# Schematic.net
KiCad netlist of a schematic drawn in EAGLE
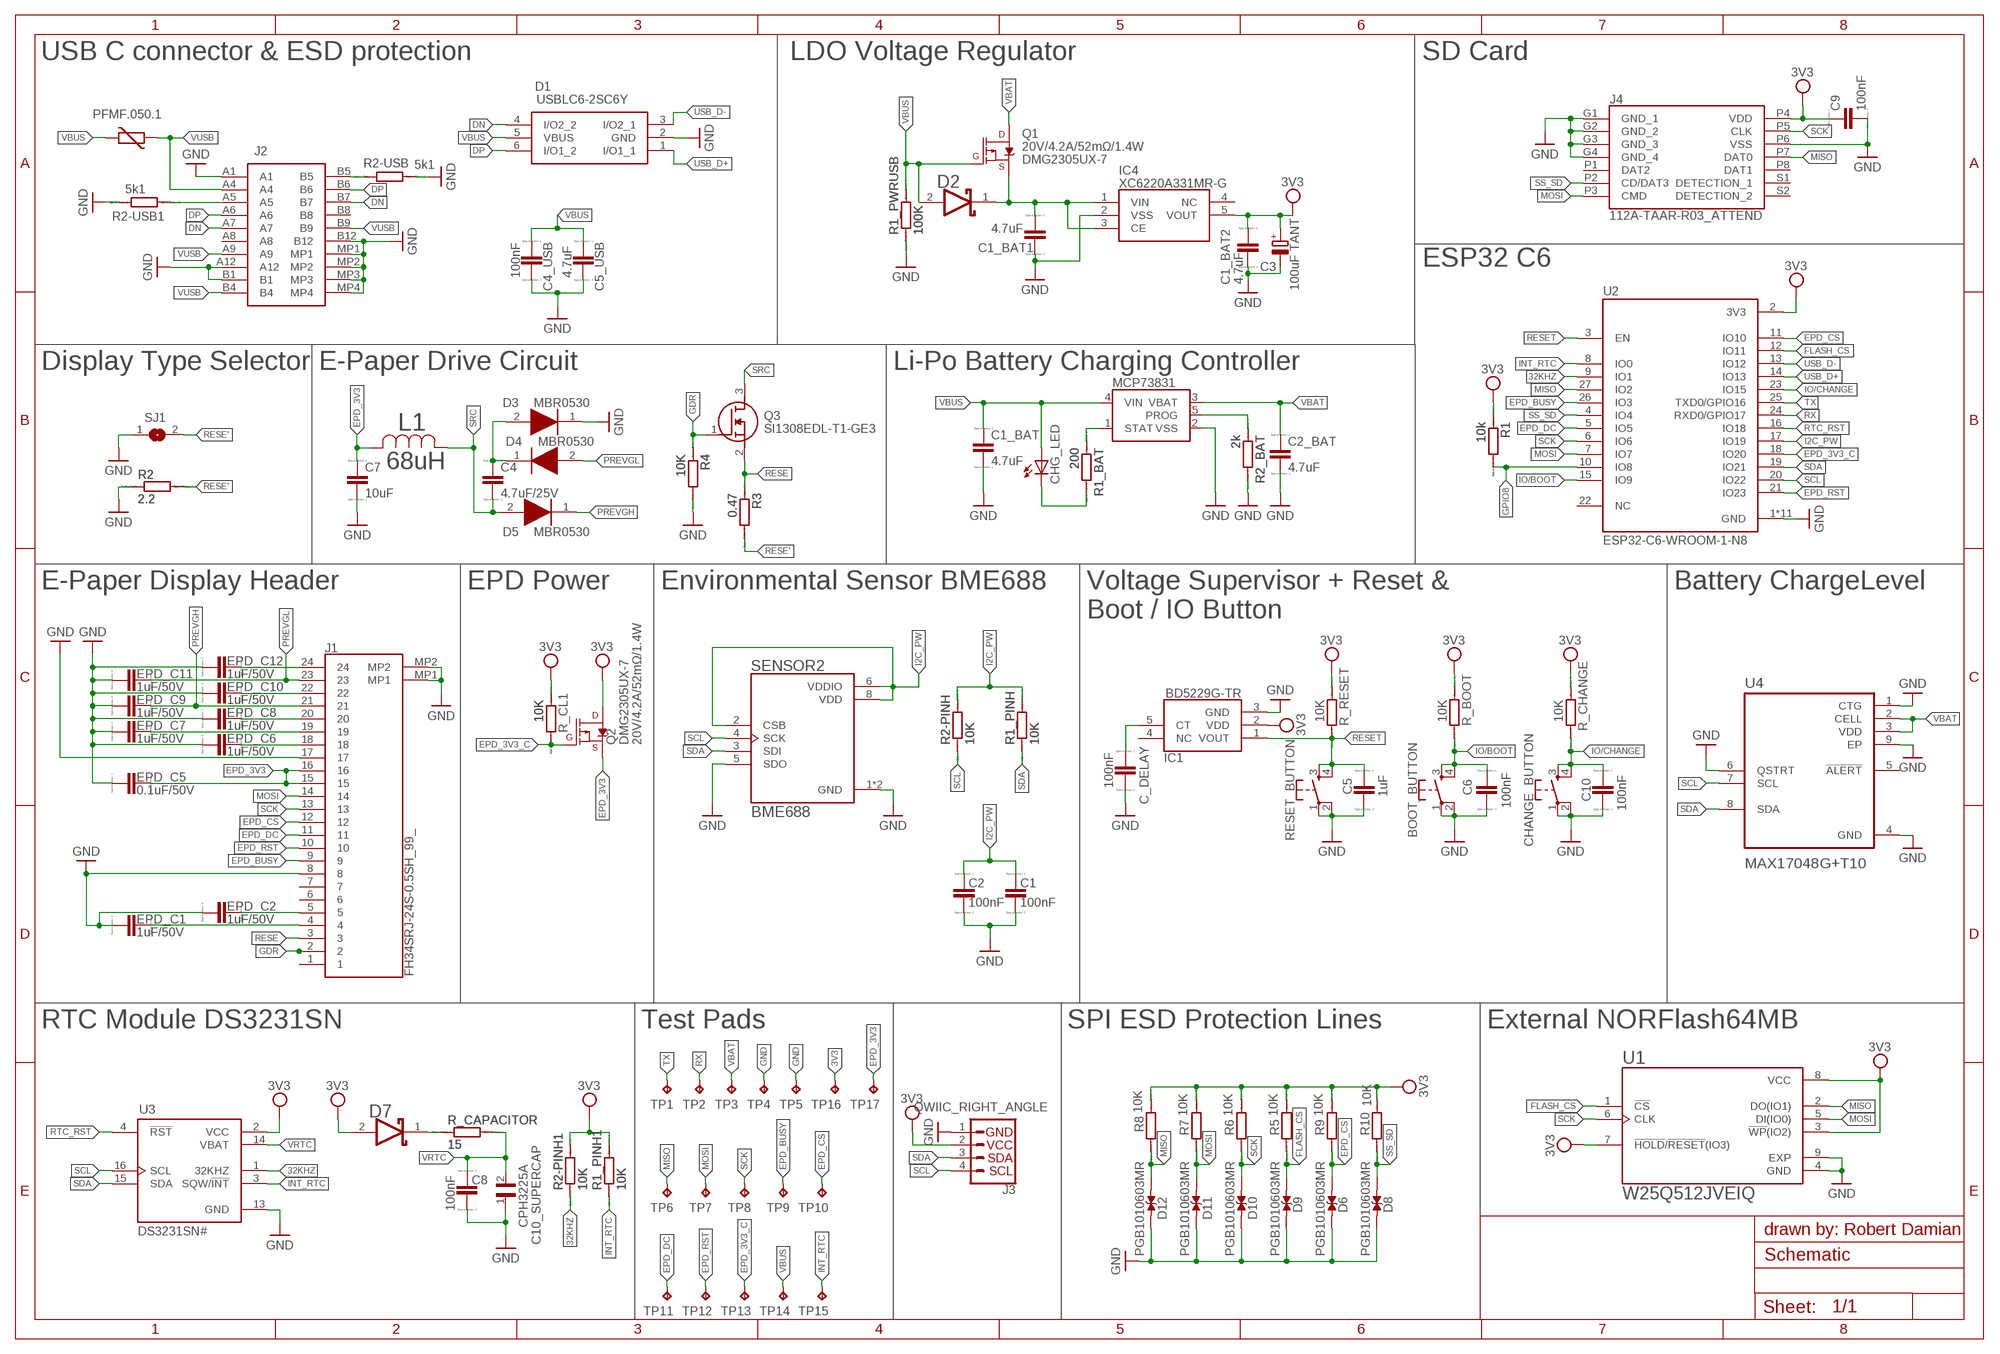
[diagram p0: schematic, sheet 1]

(export (version "E")
  (design (tool "Eeschema 10.0.6"))
  (components
    (comp (ref "BOOT_BUTTON")
      (value "BUTTON_CUSYOMV1")
      (footprint "eagle-import:MYBUTTON")
      (libsource (lib "eagle-import") (part "BUTTON_CUSYOMV1"))
    )
    (comp (ref "C1")
      (value "100nF")
      (footprint "eagle-import:EAGLE-LTSPICE_C0402")
      (libsource (lib "eagle-import") (part "EAGLE-LTSPICE_CC0402"))
    )
    (comp (ref "C1_BAT")
      (value "4.7uF")
      (footprint "eagle-import:EAGLE-LTSPICE_C0402")
      (libsource (lib "eagle-import") (part "EAGLE-LTSPICE_CC0402"))
    )
    (comp (ref "C1_BAT1")
      (value "4.7uF")
      (footprint "eagle-import:EAGLE-LTSPICE_C0402")
      (libsource (lib "eagle-import") (part "EAGLE-LTSPICE_CC0402"))
    )
    (comp (ref "C1_BAT2")
      (value "4.7uF")
      (footprint "eagle-import:EAGLE-LTSPICE_C0402")
      (libsource (lib "eagle-import") (part "EAGLE-LTSPICE_CC0402"))
    )
    (comp (ref "C2")
      (value "100nF")
      (footprint "eagle-import:EAGLE-LTSPICE_C0402")
      (libsource (lib "eagle-import") (part "EAGLE-LTSPICE_CC0402"))
    )
    (comp (ref "C2_BAT")
      (value "4.7uF")
      (footprint "eagle-import:EAGLE-LTSPICE_C0402")
      (libsource (lib "eagle-import") (part "EAGLE-LTSPICE_CC0402"))
    )
    (comp (ref "C3")
      (value "100uF TANT")
      (footprint "eagle-import:RCL_CT3528")
      (libsource (lib "eagle-import") (part "RCL_CPOL-EUCT3528"))
    )
    (comp (ref "C4")
      (value "4.7uF/25V")
      (footprint "eagle-import:EAGLE-LTSPICE_C0402")
      (libsource (lib "eagle-import") (part "EAGLE-LTSPICE_CC0402"))
    )
    (comp (ref "C4_USB")
      (value "100nF")
      (footprint "eagle-import:EAGLE-LTSPICE_C0402")
      (libsource (lib "eagle-import") (part "EAGLE-LTSPICE_CC0402"))
    )
    (comp (ref "C5")
      (value "1uF")
      (footprint "eagle-import:EAGLE-LTSPICE_C0402")
      (libsource (lib "eagle-import") (part "EAGLE-LTSPICE_CC0402"))
    )
    (comp (ref "C5_USB")
      (value "4.7uF")
      (footprint "eagle-import:EAGLE-LTSPICE_C0402")
      (libsource (lib "eagle-import") (part "EAGLE-LTSPICE_CC0402"))
    )
    (comp (ref "C6")
      (value "100nF")
      (footprint "eagle-import:EAGLE-LTSPICE_C0402")
      (libsource (lib "eagle-import") (part "EAGLE-LTSPICE_CC0402"))
    )
    (comp (ref "C7")
      (value "10uF")
      (footprint "eagle-import:EAGLE-LTSPICE_C0402")
      (libsource (lib "eagle-import") (part "EAGLE-LTSPICE_CC0402"))
    )
    (comp (ref "C8")
      (value "100nF")
      (footprint "eagle-import:EAGLE-LTSPICE_C0402")
      (libsource (lib "eagle-import") (part "EAGLE-LTSPICE_CC0402"))
    )
    (comp (ref "C9")
      (value "100nF")
      (footprint "eagle-import:EAGLE-LTSPICE_C0402")
      (libsource (lib "eagle-import") (part "EAGLE-LTSPICE_CC0402"))
    )
    (comp (ref "C10")
      (value "100nF")
      (footprint "eagle-import:EAGLE-LTSPICE_C0402")
      (libsource (lib "eagle-import") (part "EAGLE-LTSPICE_CC0402"))
    )
    (comp (ref "C10_SUPERCAP")
      (value "CPH3225A")
      (footprint "eagle-import:CAPCP3225X100N")
      (fields (field (name "MF") "Seiko Instruments"))
      (libsource (lib "eagle-import") (part "CPH3225A"))
    )
    (comp (ref "CHANGE_BUTTON")
      (value "BUTTON_CUSYOMV1")
      (footprint "eagle-import:MYBUTTON")
      (libsource (lib "eagle-import") (part "BUTTON_CUSYOMV1"))
    )
    (comp (ref "CHG_LED")
      (value "ADAFRUIT_LEDCHIP-LED0603")
      (footprint "eagle-import:ADAFRUIT_CHIP-LED0603")
      (libsource (lib "eagle-import") (part "ADAFRUIT_LEDCHIP-LED0603"))
    )
    (comp (ref "C_DELAY")
      (value "100nF")
      (footprint "eagle-import:EAGLE-LTSPICE_C0402")
      (libsource (lib "eagle-import") (part "EAGLE-LTSPICE_CC0402"))
    )
    (comp (ref "D1")
      (value "USBLC6-2SC6Y")
      (footprint "eagle-import:SOT95P280X145-6N")
      (fields (field (name "MF") "STMicroelectronics"))
      (libsource (lib "eagle-import") (part "USBLC6-2SC6Y"))
    )
    (comp (ref "D2")
      (value "SD0805S020S1R0")
      (footprint "eagle-import:ESP32_WROVER_AVX---SD0805S020S1R0_AVX_SD0805S020S1R0_0")
      (fields
        (field (name "DIGIKEY_PART_NUMBER") "478-7800-1-ND")
        (field (name "MF") "AVX")
        (field (name "MOUSER_PART_NUMBER") "581-SD0805S020S1R0")
      )
      (libsource (lib "eagle-import") (part "ESP32_WROVER_AVX---SD0805S020S1R0_AVX_SD0805S020S1R0_0_0AVX_SD0805S020S1R0_0_0"))
    )
    (comp (ref "D3")
      (value "MBR0530")
      (footprint "eagle-import:SOD3716X135N")
      (fields (field (name "MF") "ON Semiconductor"))
      (libsource (lib "eagle-import") (part "MBR0530"))
    )
    (comp (ref "D4")
      (value "MBR0530")
      (footprint "eagle-import:SOD3716X135N")
      (fields (field (name "MF") "ON Semiconductor"))
      (libsource (lib "eagle-import") (part "MBR0530"))
    )
    (comp (ref "D5")
      (value "MBR0530")
      (footprint "eagle-import:SOD3716X135N")
      (fields (field (name "MF") "ON Semiconductor"))
      (libsource (lib "eagle-import") (part "MBR0530"))
    )
    (comp (ref "D6")
      (value "PGB1010603MR")
      (footprint "eagle-import:DIOC1608X36N")
      (fields (field (name "MF") "Littelfuse Inc."))
      (libsource (lib "eagle-import") (part "PGB1010603MR"))
    )
    (comp (ref "D7")
      (value "SD0805S020S1R0")
      (footprint "eagle-import:ESP32_WROVER_AVX---SD0805S020S1R0_AVX_SD0805S020S1R0_0")
      (fields
        (field (name "DIGIKEY_PART_NUMBER") "478-7800-1-ND")
        (field (name "MF") "AVX")
        (field (name "MOUSER_PART_NUMBER") "581-SD0805S020S1R0")
      )
      (libsource (lib "eagle-import") (part "ESP32_WROVER_AVX---SD0805S020S1R0_AVX_SD0805S020S1R0_0_0AVX_SD0805S020S1R0_0_0"))
    )
    (comp (ref "D8")
      (value "PGB1010603MR")
      (footprint "eagle-import:DIOC1608X36N")
      (fields (field (name "MF") "Littelfuse Inc."))
      (libsource (lib "eagle-import") (part "PGB1010603MR"))
    )
    (comp (ref "D9")
      (value "PGB1010603MR")
      (footprint "eagle-import:DIOC1608X36N")
      (fields (field (name "MF") "Littelfuse Inc."))
      (libsource (lib "eagle-import") (part "PGB1010603MR"))
    )
    (comp (ref "D10")
      (value "PGB1010603MR")
      (footprint "eagle-import:DIOC1608X36N")
      (fields (field (name "MF") "Littelfuse Inc."))
      (libsource (lib "eagle-import") (part "PGB1010603MR"))
    )
    (comp (ref "D11")
      (value "PGB1010603MR")
      (footprint "eagle-import:DIOC1608X36N")
      (fields (field (name "MF") "Littelfuse Inc."))
      (libsource (lib "eagle-import") (part "PGB1010603MR"))
    )
    (comp (ref "D12")
      (value "PGB1010603MR")
      (footprint "eagle-import:DIOC1608X36N")
      (fields (field (name "MF") "Littelfuse Inc."))
      (libsource (lib "eagle-import") (part "PGB1010603MR"))
    )
    (comp (ref "EPD_C1")
      (value "1uF/50V")
      (footprint "eagle-import:EAGLE-LTSPICE_C0402")
      (libsource (lib "eagle-import") (part "EAGLE-LTSPICE_CC0402"))
    )
    (comp (ref "EPD_C2")
      (value "1uF/50V")
      (footprint "eagle-import:EAGLE-LTSPICE_C0402")
      (libsource (lib "eagle-import") (part "EAGLE-LTSPICE_CC0402"))
    )
    (comp (ref "EPD_C5")
      (value "0.1uF/50V")
      (footprint "eagle-import:EAGLE-LTSPICE_C0402")
      (libsource (lib "eagle-import") (part "EAGLE-LTSPICE_CC0402"))
    )
    (comp (ref "EPD_C6")
      (value "1uF/50V")
      (footprint "eagle-import:EAGLE-LTSPICE_C0402")
      (libsource (lib "eagle-import") (part "EAGLE-LTSPICE_CC0402"))
    )
    (comp (ref "EPD_C7")
      (value "1uF/50V")
      (footprint "eagle-import:EAGLE-LTSPICE_C0402")
      (libsource (lib "eagle-import") (part "EAGLE-LTSPICE_CC0402"))
    )
    (comp (ref "EPD_C8")
      (value "1uF/50V")
      (footprint "eagle-import:EAGLE-LTSPICE_C0402")
      (libsource (lib "eagle-import") (part "EAGLE-LTSPICE_CC0402"))
    )
    (comp (ref "EPD_C9")
      (value "1uF/50V")
      (footprint "eagle-import:EAGLE-LTSPICE_C0402")
      (libsource (lib "eagle-import") (part "EAGLE-LTSPICE_CC0402"))
    )
    (comp (ref "EPD_C10")
      (value "1uF/50V")
      (footprint "eagle-import:EAGLE-LTSPICE_C0402")
      (libsource (lib "eagle-import") (part "EAGLE-LTSPICE_CC0402"))
    )
    (comp (ref "EPD_C11")
      (value "1uF/50V")
      (footprint "eagle-import:EAGLE-LTSPICE_C0402")
      (libsource (lib "eagle-import") (part "EAGLE-LTSPICE_CC0402"))
    )
    (comp (ref "EPD_C12")
      (value "1uF/50V")
      (footprint "eagle-import:EAGLE-LTSPICE_C0402")
      (libsource (lib "eagle-import") (part "EAGLE-LTSPICE_CC0402"))
    )
    (comp (ref "IC1")
      (value "BD5229G-TR")
      (footprint "eagle-import:SOT95P280X125-5N")
      (fields (field (name "MOUSER_PART_NUMBER") "755-BD5229G-TR"))
      (libsource (lib "eagle-import") (part "BD5229G-TR"))
    )
    (comp (ref "IC4")
      (value "XC6220A331MR-G")
      (footprint "eagle-import:SOT95P280X120-5N")
      (fields (field (name "MOUSER_PART_NUMBER") "865-XC6220A331MR-G"))
      (libsource (lib "eagle-import") (part "XC6220A331MR-G"))
    )
    (comp (ref "J1")
      (value "FH34SRJ-24S-0.5SH_99_")
      (footprint "eagle-import:FH34SRJ24S05SH99")
      (fields
        (field (name "MANUFACTURER_PART_NUMBER") "FH34SRJ-24S-0.5SH(99)")
        (field (name "MOUSER_PART_NUMBER") "798-FH34SRJ24S05SH99")
      )
      (libsource (lib "eagle-import") (part "FH34SRJ-24S-0.5SH_99_"))
    )
    (comp (ref "J2")
      (value "SAMACSYS_PARTS_USB4110-GF-A")
      (footprint "eagle-import:SAMACSYS_PARTS_USB4110GFA")
      (fields
        (field (name "MANUFACTURER_PART_NUMBER") "USB4110-GF-A")
        (field (name "MOUSER_PART_NUMBER") "640-USB4110-GF-A")
      )
      (libsource (lib "eagle-import") (part "SAMACSYS_PARTS_USB4110-GF-A"))
    )
    (comp (ref "J3")
      (value "QWIIC_RIGHT_ANGLE")
      (footprint "eagle-import:JST04_1MM_RA")
      (libsource (lib "eagle-import") (part "QWIIC_CONNECTORJS-1MM"))
    )
    (comp (ref "J4")
      (value "112A-TAAR-R03_ATTEND")
      (footprint "eagle-import:112ATAARR03ATTEND")
      (fields (field (name "MANUFACTURER_PART_NUMBER") "112A-TAAR-R03 ATTEND"))
      (libsource (lib "eagle-import") (part "112A-TAAR-R03_ATTEND"))
    )
    (comp (ref "L1")
      (value "68uH")
      (footprint "eagle-import:IND_4828-WE-TPC_WRE")
      (fields
        (field (name "MANUFACTURER_PART_NUMBER") "744043680")
        (field (name "COPYRIGHT") "Copyright (C) 2024 Ultra Librarian. All rights reserved.")
      )
      (libsource (lib "eagle-import") (part "744043680IND_4828-WE-TPC_WRE"))
    )
    (comp (ref "MCP73831")
      (value "ESP32_WROVER_SPARKFUN-IC-POWER_MCP73831")
      (footprint "eagle-import:ESP32_WROVER_SPARKFUN-IC-POWER_SOT23-5")
      (libsource (lib "eagle-import") (part "ESP32_WROVER_SPARKFUN-IC-POWER_MCP73831"))
    )
    (comp (ref "PFMF.050.1")
      (value "ESP32C6_VARISTORCN1812")
      (footprint "eagle-import:ESP32C6_VARISTOR_CT_CN1812")
      (libsource (lib "eagle-import") (part "ESP32C6_VARISTORCN1812"))
    )
    (comp (ref "Q1")
      (value "20V/4.2A/52mΩ/1.4W")
      (footprint "eagle-import:ESP32_WROVER_SPARKFUN-DISCRETESEMI_SOT23-3")
      (libsource (lib "eagle-import") (part "ESP32_WROVER_SPARKFUN-DISCRETESEMI_MOSFET_PCH-DMG2305UX-7"))
    )
    (comp (ref "Q2")
      (value "20V/4.2A/52mΩ/1.4W")
      (footprint "eagle-import:ESP32_WROVER_SPARKFUN-DISCRETESEMI_SOT23-3")
      (libsource (lib "eagle-import") (part "ESP32_WROVER_SPARKFUN-DISCRETESEMI_MOSFET_PCH-DMG2305UX-7"))
    )
    (comp (ref "Q3")
      (value "SI1308EDL-T1-GE3")
      (footprint "eagle-import:SOT65P210X110-3N")
      (fields (field (name "MF") "Vishay Siliconix"))
      (libsource (lib "eagle-import") (part "SI1308EDL-T1-GE3"))
    )
    (comp (ref "R1")
      (value "10k")
      (footprint "eagle-import:ESP32_WROVER_EAGLE-LTSPICE_R0402")
      (libsource (lib "eagle-import") (part "ESP32_WROVER_EAGLE-LTSPICE_RR0402"))
    )
    (comp (ref "R1_BAT")
      (value "200")
      (footprint "eagle-import:ESP32_WROVER_EAGLE-LTSPICE_R0402")
      (libsource (lib "eagle-import") (part "ESP32_WROVER_EAGLE-LTSPICE_RR0402"))
    )
    (comp (ref "R1_PINH")
      (value "10K")
      (footprint "eagle-import:ESP32_WROVER_EAGLE-LTSPICE_R0402")
      (libsource (lib "eagle-import") (part "ESP32_WROVER_EAGLE-LTSPICE_RR0402"))
    )
    (comp (ref "R1_PINH1")
      (value "10K")
      (footprint "eagle-import:ESP32_WROVER_EAGLE-LTSPICE_R0402")
      (libsource (lib "eagle-import") (part "ESP32_WROVER_EAGLE-LTSPICE_RR0402"))
    )
    (comp (ref "R1_PWRUSB")
      (value "100K")
      (footprint "eagle-import:ESP32_WROVER_EAGLE-LTSPICE_R0402")
      (libsource (lib "eagle-import") (part "ESP32_WROVER_EAGLE-LTSPICE_RR0402"))
    )
    (comp (ref "R2")
      (value "2.2")
      (footprint "eagle-import:ESP32_WROVER_EAGLE-LTSPICE_R0402")
      (libsource (lib "eagle-import") (part "ESP32_WROVER_EAGLE-LTSPICE_RR0402"))
    )
    (comp (ref "R2-PINH")
      (value "10K")
      (footprint "eagle-import:ESP32_WROVER_EAGLE-LTSPICE_R0402")
      (libsource (lib "eagle-import") (part "ESP32_WROVER_EAGLE-LTSPICE_RR0402"))
    )
    (comp (ref "R2-PINH1")
      (value "10K")
      (footprint "eagle-import:ESP32_WROVER_EAGLE-LTSPICE_R0402")
      (libsource (lib "eagle-import") (part "ESP32_WROVER_EAGLE-LTSPICE_RR0402"))
    )
    (comp (ref "R2-USB")
      (value "5k1")
      (footprint "eagle-import:ESP32_WROVER_EAGLE-LTSPICE_R0402")
      (libsource (lib "eagle-import") (part "ESP32_WROVER_EAGLE-LTSPICE_RR0402"))
    )
    (comp (ref "R2-USB1")
      (value "5k1")
      (footprint "eagle-import:ESP32_WROVER_EAGLE-LTSPICE_R0402")
      (libsource (lib "eagle-import") (part "ESP32_WROVER_EAGLE-LTSPICE_RR0402"))
    )
    (comp (ref "R2_BAT")
      (value "2k")
      (footprint "eagle-import:ESP32_WROVER_EAGLE-LTSPICE_R0402")
      (libsource (lib "eagle-import") (part "ESP32_WROVER_EAGLE-LTSPICE_RR0402"))
    )
    (comp (ref "R3")
      (value "0.47")
      (footprint "eagle-import:ESP32_WROVER_EAGLE-LTSPICE_R0402")
      (libsource (lib "eagle-import") (part "ESP32_WROVER_EAGLE-LTSPICE_RR0402"))
    )
    (comp (ref "R4")
      (value "10K")
      (footprint "eagle-import:ESP32_WROVER_EAGLE-LTSPICE_R0402")
      (libsource (lib "eagle-import") (part "ESP32_WROVER_EAGLE-LTSPICE_RR0402"))
    )
    (comp (ref "R5")
      (value "10K")
      (footprint "eagle-import:ESP32_WROVER_EAGLE-LTSPICE_R0402")
      (libsource (lib "eagle-import") (part "ESP32_WROVER_EAGLE-LTSPICE_RR0402"))
    )
    (comp (ref "R6")
      (value "10K")
      (footprint "eagle-import:ESP32_WROVER_EAGLE-LTSPICE_R0402")
      (libsource (lib "eagle-import") (part "ESP32_WROVER_EAGLE-LTSPICE_RR0402"))
    )
    (comp (ref "R7")
      (value "10K")
      (footprint "eagle-import:ESP32_WROVER_EAGLE-LTSPICE_R0402")
      (libsource (lib "eagle-import") (part "ESP32_WROVER_EAGLE-LTSPICE_RR0402"))
    )
    (comp (ref "R8")
      (value "10K")
      (footprint "eagle-import:ESP32_WROVER_EAGLE-LTSPICE_R0402")
      (libsource (lib "eagle-import") (part "ESP32_WROVER_EAGLE-LTSPICE_RR0402"))
    )
    (comp (ref "R9")
      (value "10K")
      (footprint "eagle-import:ESP32_WROVER_EAGLE-LTSPICE_R0402")
      (libsource (lib "eagle-import") (part "ESP32_WROVER_EAGLE-LTSPICE_RR0402"))
    )
    (comp (ref "R10")
      (value "10K")
      (footprint "eagle-import:ESP32_WROVER_EAGLE-LTSPICE_R0402")
      (libsource (lib "eagle-import") (part "ESP32_WROVER_EAGLE-LTSPICE_RR0402"))
    )
    (comp (ref "RESET_BUTTON")
      (value "BUTTON_CUSYOMV1")
      (footprint "eagle-import:MYBUTTON")
      (libsource (lib "eagle-import") (part "BUTTON_CUSYOMV1"))
    )
    (comp (ref "R_BOOT")
      (value "10K")
      (footprint "eagle-import:ESP32_WROVER_EAGLE-LTSPICE_R0402")
      (libsource (lib "eagle-import") (part "ESP32_WROVER_EAGLE-LTSPICE_RR0402"))
    )
    (comp (ref "R_CAPACITOR")
      (value "15")
      (footprint "eagle-import:ESP32_WROVER_EAGLE-LTSPICE_R0402")
      (libsource (lib "eagle-import") (part "ESP32_WROVER_EAGLE-LTSPICE_RR0402"))
    )
    (comp (ref "R_CHANGE")
      (value "10K")
      (footprint "eagle-import:ESP32_WROVER_EAGLE-LTSPICE_R0402")
      (libsource (lib "eagle-import") (part "ESP32_WROVER_EAGLE-LTSPICE_RR0402"))
    )
    (comp (ref "R_CL1")
      (value "10K")
      (footprint "eagle-import:ESP32_WROVER_EAGLE-LTSPICE_R0402")
      (libsource (lib "eagle-import") (part "ESP32_WROVER_EAGLE-LTSPICE_RR0402"))
    )
    (comp (ref "R_RESET")
      (value "10K")
      (footprint "eagle-import:ESP32_WROVER_EAGLE-LTSPICE_R0402")
      (libsource (lib "eagle-import") (part "ESP32_WROVER_EAGLE-LTSPICE_RR0402"))
    )
    (comp (ref "SENSOR2")
      (value "BME688")
      (footprint "eagle-import:ESP32_WROVER_BME680_PSON80P300X300X100-8N")
      (fields (field (name "MF") "Bosch Sensortec") (field (name "MP") "BME680"))
      (libsource (lib "eagle-import") (part "ESP32_WROVER_BME680_BME680"))
    )
    (comp (ref "SJ1")
      (value "SJ")
      (footprint "eagle-import:ESP32_WROVER_EAGLE-LTSPICE_R0402")
      (libsource (lib "eagle-import") (part "SJ"))
    )
    (comp (ref "TP1")
      (value "TPTP20R")
      (footprint "eagle-import:TP20R")
      (libsource (lib "eagle-import") (part "TPTP20R"))
    )
    (comp (ref "TP2")
      (value "TPTP20R")
      (footprint "eagle-import:TP20R")
      (libsource (lib "eagle-import") (part "TPTP20R"))
    )
    (comp (ref "TP3")
      (value "TPTP20R")
      (footprint "eagle-import:TP20R")
      (libsource (lib "eagle-import") (part "TPTP20R"))
    )
    (comp (ref "TP4")
      (value "TPTP20R")
      (footprint "eagle-import:TP20R")
      (libsource (lib "eagle-import") (part "TPTP20R"))
    )
    (comp (ref "TP5")
      (value "TPTP20R")
      (footprint "eagle-import:TP20R")
      (libsource (lib "eagle-import") (part "TPTP20R"))
    )
    (comp (ref "TP6")
      (value "TPTP20R")
      (footprint "eagle-import:TP20R")
      (libsource (lib "eagle-import") (part "TPTP20R"))
    )
    (comp (ref "TP7")
      (value "TPTP20R")
      (footprint "eagle-import:TP20R")
      (libsource (lib "eagle-import") (part "TPTP20R"))
    )
    (comp (ref "TP8")
      (value "TPTP20R")
      (footprint "eagle-import:TP20R")
      (libsource (lib "eagle-import") (part "TPTP20R"))
    )
    (comp (ref "TP9")
      (value "TPTP20R")
      (footprint "eagle-import:TP20R")
      (libsource (lib "eagle-import") (part "TPTP20R"))
    )
    (comp (ref "TP10")
      (value "TPTP20R")
      (footprint "eagle-import:TP20R")
      (libsource (lib "eagle-import") (part "TPTP20R"))
    )
    (comp (ref "TP11")
      (value "TPTP20R")
      (footprint "eagle-import:TP20R")
      (libsource (lib "eagle-import") (part "TPTP20R"))
    )
    (comp (ref "TP12")
      (value "TPTP20R")
      (footprint "eagle-import:TP20R")
      (libsource (lib "eagle-import") (part "TPTP20R"))
    )
    (comp (ref "TP13")
      (value "TPTP20R")
      (footprint "eagle-import:TP20R")
      (libsource (lib "eagle-import") (part "TPTP20R"))
    )
    (comp (ref "TP14")
      (value "TPTP20R")
      (footprint "eagle-import:TP20R")
      (libsource (lib "eagle-import") (part "TPTP20R"))
    )
    (comp (ref "TP15")
      (value "TPTP20R")
      (footprint "eagle-import:TP20R")
      (libsource (lib "eagle-import") (part "TPTP20R"))
    )
    (comp (ref "TP16")
      (value "TPTP20R")
      (footprint "eagle-import:TP20R")
      (libsource (lib "eagle-import") (part "TPTP20R"))
    )
    (comp (ref "TP17")
      (value "TPTP20R")
      (footprint "eagle-import:TP20R")
      (libsource (lib "eagle-import") (part "TPTP20R"))
    )
    (comp (ref "U1")
      (value "W25Q512JVEIQ")
      (footprint "eagle-import:SON127P600X800X80-9N")
      (fields (field (name "MF") "Winbond Electronics"))
      (libsource (lib "eagle-import") (part "W25Q512JVEIQ"))
    )
    (comp (ref "U2")
      (value "ESP32-C6-WROOM-1-N8")
      (footprint "eagle-import:XCVR_ESP32-C6-WROOM-1-N8")
      (fields (field (name "MF") "Espressif Systems"))
      (libsource (lib "eagle-import") (part "ESP32-C6-WROOM-1-N8"))
    )
    (comp (ref "U3")
      (value "DS3231SN#")
      (footprint "eagle-import:SOIC127P1032X265-16N")
      (fields (field (name "MF") "Analog Devices"))
      (libsource (lib "eagle-import") (part "DS3231SN#"))
    )
    (comp (ref "U4")
      (value "MAX17048G+T10")
      (footprint "eagle-import:SON50P200X200X80-9N")
      (fields (field (name "MF") "Analog Devices"))
      (libsource (lib "eagle-import") (part "MAX17048G+T10"))
    )
  )
  (nets
    (net (code "1") (name "3V3") (class "Default")
      (node (ref "C1_BAT2") (pin "1") (pinfunction "1_1") (pintype "passive"))
      (node (ref "C3") (pin "+") (pinfunction "+_+") (pintype "passive"))
      (node (ref "C9") (pin "1") (pinfunction "1_1") (pintype "passive"))
      (node (ref "D7") (pin "2") (pinfunction "ANODE_2") (pintype "bidirectional"))
      (node (ref "IC1") (pin "2") (pinfunction "VDD_2") (pintype "bidirectional"))
      (node (ref "IC4") (pin "5") (pinfunction "VOUT_5") (pintype "bidirectional"))
      (node (ref "J3") (pin "2") (pinfunction "2_2") (pintype "power_in"))
      (node (ref "J4") (pin "P4") (pinfunction "VDD_P4") (pintype "bidirectional"))
      (node (ref "Q2") (pin "3") (pinfunction "D_3") (pintype "bidirectional"))
      (node (ref "R1") (pin "1") (pinfunction "1_1") (pintype "passive"))
      (node (ref "R10") (pin "2") (pinfunction "2_2") (pintype "passive"))
      (node (ref "R1_PINH1") (pin "2") (pinfunction "2_2") (pintype "passive"))
      (node (ref "R2-PINH1") (pin "2") (pinfunction "2_2") (pintype "passive"))
      (node (ref "R5") (pin "2") (pinfunction "2_2") (pintype "passive"))
      (node (ref "R6") (pin "2") (pinfunction "2_2") (pintype "passive"))
      (node (ref "R7") (pin "2") (pinfunction "2_2") (pintype "passive"))
      (node (ref "R8") (pin "2") (pinfunction "2_2") (pintype "passive"))
      (node (ref "R9") (pin "2") (pinfunction "2_2") (pintype "passive"))
      (node (ref "R_BOOT") (pin "1") (pinfunction "1_1") (pintype "passive"))
      (node (ref "R_CHANGE") (pin "1") (pinfunction "1_1") (pintype "passive"))
      (node (ref "R_CL1") (pin "1") (pinfunction "1_1") (pintype "passive"))
      (node (ref "R_RESET") (pin "1") (pinfunction "1_1") (pintype "passive"))
      (node (ref "TP16") (pin "TP") (pinfunction "TP_TP") (pintype "input"))
      (node (ref "U1") (pin "3") (pinfunction "~{WP}(IO2)_3") (pintype "bidirectional"))
      (node (ref "U1") (pin "7") (pinfunction "~{HOLD}/~{RESET}(IO3)_7") (pintype "bidirectional"))
      (node (ref "U1") (pin "8") (pinfunction "VCC_8") (pintype "power_in"))
      (node (ref "U2") (pin "2") (pinfunction "3V3_2") (pintype "power_in"))
      (node (ref "U3") (pin "2") (pinfunction "VCC_2") (pintype "power_in"))
    )
    (net (code "2") (name "32KHZ") (class "Default")
      (node (ref "R2-PINH1") (pin "1") (pinfunction "1_1") (pintype "passive"))
      (node (ref "U2") (pin "9") (pinfunction "IO1_9") (pintype "bidirectional"))
      (node (ref "U3") (pin "1") (pinfunction "32KHZ_1") (pintype "output"))
    )
    (net (code "3") (name "DN") (class "Default")
      (node (ref "D1") (pin "4") (pinfunction "I/O2_2_4") (pintype "bidirectional"))
      (node (ref "J2") (pin "A7") (pinfunction "A7_A7") (pintype "bidirectional"))
      (node (ref "J2") (pin "B7") (pinfunction "B7_B7") (pintype "bidirectional"))
    )
    (net (code "4") (name "DP") (class "Default")
      (node (ref "D1") (pin "6") (pinfunction "I/O1_2_6") (pintype "bidirectional"))
      (node (ref "J2") (pin "A6") (pinfunction "A6_A6") (pintype "bidirectional"))
      (node (ref "J2") (pin "B6") (pinfunction "B6_B6") (pintype "bidirectional"))
    )
    (net (code "5") (name "EPD_3V3") (class "Default")
      (node (ref "C7") (pin "1") (pinfunction "1_1") (pintype "passive"))
      (node (ref "EPD_C5") (pin "1") (pinfunction "1_1") (pintype "passive"))
      (node (ref "J1") (pin "15") (pinfunction "15_15") (pintype "bidirectional"))
      (node (ref "J1") (pin "16") (pinfunction "16_16") (pintype "bidirectional"))
      (node (ref "L1") (pin "2") (pinfunction "2_2") (pintype "passive"))
      (node (ref "Q2") (pin "2") (pinfunction "S_2") (pintype "bidirectional"))
      (node (ref "TP17") (pin "TP") (pinfunction "TP_TP") (pintype "input"))
    )
    (net (code "6") (name "EPD_3V3_C") (class "Default")
      (node (ref "Q2") (pin "1") (pinfunction "G_1") (pintype "bidirectional"))
      (node (ref "R_CL1") (pin "2") (pinfunction "2_2") (pintype "passive"))
      (node (ref "TP13") (pin "TP") (pinfunction "TP_TP") (pintype "input"))
      (node (ref "U2") (pin "18") (pinfunction "IO20_18") (pintype "bidirectional"))
    )
    (net (code "7") (name "EPD_BUSY") (class "Default")
      (node (ref "J1") (pin "9") (pinfunction "9_9") (pintype "bidirectional"))
      (node (ref "TP9") (pin "TP") (pinfunction "TP_TP") (pintype "input"))
      (node (ref "U2") (pin "26") (pinfunction "IO3_26") (pintype "bidirectional"))
    )
    (net (code "8") (name "EPD_CS") (class "Default")
      (node (ref "D6") (pin "1") (pinfunction "1_1") (pintype "passive"))
      (node (ref "J1") (pin "12") (pinfunction "12_12") (pintype "bidirectional"))
      (node (ref "R9") (pin "1") (pinfunction "1_1") (pintype "passive"))
      (node (ref "TP10") (pin "TP") (pinfunction "TP_TP") (pintype "input"))
      (node (ref "U2") (pin "11") (pinfunction "IO10_11") (pintype "bidirectional"))
    )
    (net (code "9") (name "EPD_DC") (class "Default")
      (node (ref "J1") (pin "11") (pinfunction "11_11") (pintype "bidirectional"))
      (node (ref "TP11") (pin "TP") (pinfunction "TP_TP") (pintype "input"))
      (node (ref "U2") (pin "5") (pinfunction "IO5_5") (pintype "bidirectional"))
    )
    (net (code "10") (name "EPD_RST") (class "Default")
      (node (ref "J1") (pin "10") (pinfunction "10_10") (pintype "bidirectional"))
      (node (ref "TP12") (pin "TP") (pinfunction "TP_TP") (pintype "input"))
      (node (ref "U2") (pin "21") (pinfunction "IO23_21") (pintype "bidirectional"))
    )
    (net (code "11") (name "FLASH_CS") (class "Default")
      (node (ref "D9") (pin "1") (pinfunction "1_1") (pintype "passive"))
      (node (ref "R5") (pin "1") (pinfunction "1_1") (pintype "passive"))
      (node (ref "U1") (pin "1") (pinfunction "~{CS}_1") (pintype "input"))
      (node (ref "U2") (pin "12") (pinfunction "IO11_12") (pintype "bidirectional"))
    )
    (net (code "12") (name "GDR") (class "Default")
      (node (ref "J1") (pin "2") (pinfunction "2_2") (pintype "bidirectional"))
      (node (ref "Q3") (pin "1") (pinfunction "G_1") (pintype "bidirectional"))
      (node (ref "R4") (pin "1") (pinfunction "1_1") (pintype "passive"))
    )
    (net (code "13") (name "GND") (class "Default")
      (node (ref "BOOT_BUTTON") (pin "1") (pinfunction "1_1") (pintype "passive"))
      (node (ref "BOOT_BUTTON") (pin "2") (pinfunction "2_2") (pintype "passive"))
      (node (ref "C1") (pin "2") (pinfunction "2_2") (pintype "passive"))
      (node (ref "C10") (pin "2") (pinfunction "2_2") (pintype "passive"))
      (node (ref "C10_SUPERCAP") (pin "1") (pinfunction "1_1") (pintype "passive"))
      (node (ref "C1_BAT") (pin "2") (pinfunction "2_2") (pintype "passive"))
      (node (ref "C1_BAT1") (pin "2") (pinfunction "2_2") (pintype "passive"))
      (node (ref "C1_BAT2") (pin "2") (pinfunction "2_2") (pintype "passive"))
      (node (ref "C2") (pin "2") (pinfunction "2_2") (pintype "passive"))
      (node (ref "C2_BAT") (pin "2") (pinfunction "2_2") (pintype "passive"))
      (node (ref "C3") (pin "-") (pinfunction "-_-") (pintype "passive"))
      (node (ref "C4_USB") (pin "2") (pinfunction "2_2") (pintype "passive"))
      (node (ref "C5") (pin "2") (pinfunction "2_2") (pintype "passive"))
      (node (ref "C5_USB") (pin "2") (pinfunction "2_2") (pintype "passive"))
      (node (ref "C6") (pin "2") (pinfunction "2_2") (pintype "passive"))
      (node (ref "C7") (pin "2") (pinfunction "2_2") (pintype "passive"))
      (node (ref "C8") (pin "2") (pinfunction "2_2") (pintype "passive"))
      (node (ref "C9") (pin "2") (pinfunction "2_2") (pintype "passive"))
      (node (ref "CHANGE_BUTTON") (pin "1") (pinfunction "1_1") (pintype "passive"))
      (node (ref "CHANGE_BUTTON") (pin "2") (pinfunction "2_2") (pintype "passive"))
      (node (ref "C_DELAY") (pin "2") (pinfunction "2_2") (pintype "passive"))
      (node (ref "D1") (pin "2") (pinfunction "GND_2") (pintype "bidirectional"))
      (node (ref "D10") (pin "2") (pinfunction "2_2") (pintype "passive"))
      (node (ref "D11") (pin "2") (pinfunction "2_2") (pintype "passive"))
      (node (ref "D12") (pin "2") (pinfunction "2_2") (pintype "passive"))
      (node (ref "D3") (pin "1") (pinfunction "K_1") (pintype "bidirectional"))
      (node (ref "D6") (pin "2") (pinfunction "2_2") (pintype "passive"))
      (node (ref "D8") (pin "2") (pinfunction "2_2") (pintype "passive"))
      (node (ref "D9") (pin "2") (pinfunction "2_2") (pintype "passive"))
      (node (ref "EPD_C1") (pin "2") (pinfunction "2_2") (pintype "passive"))
      (node (ref "EPD_C10") (pin "2") (pinfunction "2_2") (pintype "passive"))
      (node (ref "EPD_C11") (pin "2") (pinfunction "2_2") (pintype "passive"))
      (node (ref "EPD_C12") (pin "2") (pinfunction "2_2") (pintype "passive"))
      (node (ref "EPD_C2") (pin "2") (pinfunction "2_2") (pintype "passive"))
      (node (ref "EPD_C5") (pin "2") (pinfunction "2_2") (pintype "passive"))
      (node (ref "EPD_C6") (pin "2") (pinfunction "2_2") (pintype "passive"))
      (node (ref "EPD_C7") (pin "2") (pinfunction "2_2") (pintype "passive"))
      (node (ref "EPD_C8") (pin "2") (pinfunction "2_2") (pintype "passive"))
      (node (ref "EPD_C9") (pin "2") (pinfunction "2_2") (pintype "passive"))
      (node (ref "IC1") (pin "3") (pinfunction "GND_3") (pintype "bidirectional"))
      (node (ref "IC4") (pin "2") (pinfunction "VSS_2") (pintype "bidirectional"))
      (node (ref "J1") (pin "17") (pinfunction "17_17") (pintype "bidirectional"))
      (node (ref "J1") (pin "8") (pinfunction "8_8") (pintype "bidirectional"))
      (node (ref "J1") (pin "MP1") (pinfunction "MP1_MP1") (pintype "bidirectional"))
      (node (ref "J1") (pin "MP2") (pinfunction "MP2_MP2") (pintype "bidirectional"))
      (node (ref "J2") (pin "A1") (pinfunction "A1_A1") (pintype "bidirectional"))
      (node (ref "J2") (pin "A12") (pinfunction "A12_A12") (pintype "bidirectional"))
      (node (ref "J2") (pin "B1") (pinfunction "B1_B1") (pintype "bidirectional"))
      (node (ref "J2") (pin "B12") (pinfunction "B12_B12") (pintype "bidirectional"))
      (node (ref "J2") (pin "MP1") (pinfunction "MP1_MP1") (pintype "bidirectional"))
      (node (ref "J2") (pin "MP2") (pinfunction "MP2_MP2") (pintype "bidirectional"))
      (node (ref "J2") (pin "MP3") (pinfunction "MP3_MP3") (pintype "bidirectional"))
      (node (ref "J2") (pin "MP4") (pinfunction "MP4_MP4") (pintype "bidirectional"))
      (node (ref "J3") (pin "1") (pinfunction "1_1") (pintype "power_in"))
      (node (ref "J4") (pin "G1") (pinfunction "GND_1_G1") (pintype "bidirectional"))
      (node (ref "J4") (pin "G2") (pinfunction "GND_2_G2") (pintype "bidirectional"))
      (node (ref "J4") (pin "G3") (pinfunction "GND_3_G3") (pintype "bidirectional"))
      (node (ref "J4") (pin "G4") (pinfunction "GND_4_G4") (pintype "bidirectional"))
      (node (ref "J4") (pin "P6") (pinfunction "VSS_P6") (pintype "bidirectional"))
      (node (ref "MCP73831") (pin "2") (pinfunction "VSS_2") (pintype "power_in"))
      (node (ref "R1_PWRUSB") (pin "1") (pinfunction "1_1") (pintype "passive"))
      (node (ref "R2") (pin "1") (pinfunction "1_1") (pintype "passive"))
      (node (ref "R2-USB") (pin "1") (pinfunction "1_1") (pintype "passive"))
      (node (ref "R2-USB1") (pin "1") (pinfunction "1_1") (pintype "passive"))
      (node (ref "R2_BAT") (pin "2") (pinfunction "2_2") (pintype "passive"))
      (node (ref "R4") (pin "2") (pinfunction "2_2") (pintype "passive"))
      (node (ref "RESET_BUTTON") (pin "1") (pinfunction "1_1") (pintype "passive"))
      (node (ref "RESET_BUTTON") (pin "2") (pinfunction "2_2") (pintype "passive"))
      (node (ref "SENSOR2") (pin "1") (pinfunction "GND_1") (pintype "power_in"))
      (node (ref "SENSOR2") (pin "5") (pinfunction "SDO_5") (pintype "bidirectional"))
      (node (ref "SENSOR2") (pin "7") (pinfunction "GND_7") (pintype "power_in"))
      (node (ref "SJ1") (pin "1") (pinfunction "1_1") (pintype "passive"))
      (node (ref "TP4") (pin "TP") (pinfunction "TP_TP") (pintype "input"))
      (node (ref "TP5") (pin "TP") (pinfunction "TP_TP") (pintype "input"))
      (node (ref "U1") (pin "4") (pinfunction "GND_4") (pintype "power_in"))
      (node (ref "U1") (pin "9") (pinfunction "EXP_9") (pintype "passive"))
      (node (ref "U2") (pin "1") (pinfunction "GND_1") (pintype "power_in"))
      (node (ref "U2") (pin "28") (pinfunction "GND_28") (pintype "power_in"))
      (node (ref "U2") (pin "29_1") (pinfunction "GND_29_1") (pintype "power_in"))
      (node (ref "U2") (pin "29_2") (pinfunction "GND_29_2") (pintype "power_in"))
      (node (ref "U2") (pin "29_3") (pinfunction "GND_29_3") (pintype "power_in"))
      (node (ref "U2") (pin "29_4") (pinfunction "GND_29_4") (pintype "power_in"))
      (node (ref "U2") (pin "29_5") (pinfunction "GND_29_5") (pintype "power_in"))
      (node (ref "U2") (pin "29_6") (pinfunction "GND_29_6") (pintype "power_in"))
      (node (ref "U2") (pin "29_7") (pinfunction "GND_29_7") (pintype "power_in"))
      (node (ref "U2") (pin "29_8") (pinfunction "GND_29_8") (pintype "power_in"))
      (node (ref "U2") (pin "29_9") (pinfunction "GND_29_9") (pintype "power_in"))
      (node (ref "U3") (pin "13") (pinfunction "GND_13") (pintype "power_in"))
      (node (ref "U4") (pin "1") (pinfunction "CTG_1") (pintype "power_in"))
      (node (ref "U4") (pin "4") (pinfunction "GND_4") (pintype "power_in"))
      (node (ref "U4") (pin "6") (pinfunction "QSTRT_6") (pintype "input"))
      (node (ref "U4") (pin "9") (pinfunction "EP_9") (pintype "power_in"))
    )
    (net (code "14") (name "GPIO8") (class "Default")
      (node (ref "R1") (pin "2") (pinfunction "2_2") (pintype "passive"))
      (node (ref "U2") (pin "10") (pinfunction "IO8_10") (pintype "bidirectional"))
    )
    (net (code "15") (name "I2C_PW") (class "Default")
      (node (ref "C1") (pin "1") (pinfunction "1_1") (pintype "passive"))
      (node (ref "C2") (pin "1") (pinfunction "1_1") (pintype "passive"))
      (node (ref "R1_PINH") (pin "2") (pinfunction "2_2") (pintype "passive"))
      (node (ref "R2-PINH") (pin "2") (pinfunction "2_2") (pintype "passive"))
      (node (ref "SENSOR2") (pin "2") (pinfunction "CSB_2") (pintype "input"))
      (node (ref "SENSOR2") (pin "6") (pinfunction "VDDIO_6") (pintype "power_in"))
      (node (ref "SENSOR2") (pin "8") (pinfunction "VDD_8") (pintype "power_in"))
      (node (ref "U2") (pin "17") (pinfunction "IO19_17") (pintype "bidirectional"))
    )
    (net (code "16") (name "INT_RTC") (class "Default")
      (node (ref "R1_PINH1") (pin "1") (pinfunction "1_1") (pintype "passive"))
      (node (ref "TP15") (pin "TP") (pinfunction "TP_TP") (pintype "input"))
      (node (ref "U2") (pin "8") (pinfunction "IO0_8") (pintype "bidirectional"))
      (node (ref "U3") (pin "3") (pinfunction "SQW/~{INT}_3") (pintype "output"))
    )
    (net (code "17") (name "IO{slash}BOOT") (class "Default")
      (node (ref "BOOT_BUTTON") (pin "3") (pinfunction "3_3") (pintype "passive"))
      (node (ref "BOOT_BUTTON") (pin "4") (pinfunction "4_4") (pintype "passive"))
      (node (ref "C6") (pin "1") (pinfunction "1_1") (pintype "passive"))
      (node (ref "R_BOOT") (pin "2") (pinfunction "2_2") (pintype "passive"))
      (node (ref "U2") (pin "15") (pinfunction "IO9_15") (pintype "bidirectional"))
    )
    (net (code "18") (name "IO{slash}CHANGE") (class "Default")
      (node (ref "C10") (pin "1") (pinfunction "1_1") (pintype "passive"))
      (node (ref "CHANGE_BUTTON") (pin "3") (pinfunction "3_3") (pintype "passive"))
      (node (ref "CHANGE_BUTTON") (pin "4") (pinfunction "4_4") (pintype "passive"))
      (node (ref "R_CHANGE") (pin "2") (pinfunction "2_2") (pintype "passive"))
      (node (ref "U2") (pin "23") (pinfunction "IO15_23") (pintype "bidirectional"))
    )
    (net (code "19") (name "MISO") (class "Default")
      (node (ref "D12") (pin "1") (pinfunction "1_1") (pintype "passive"))
      (node (ref "J4") (pin "P7") (pinfunction "DAT0_P7") (pintype "bidirectional"))
      (node (ref "R8") (pin "1") (pinfunction "1_1") (pintype "passive"))
      (node (ref "TP6") (pin "TP") (pinfunction "TP_TP") (pintype "input"))
      (node (ref "U1") (pin "2") (pinfunction "DO(IO1)_2") (pintype "bidirectional"))
      (node (ref "U2") (pin "27") (pinfunction "IO2_27") (pintype "bidirectional"))
    )
    (net (code "20") (name "MOSI") (class "Default")
      (node (ref "D11") (pin "1") (pinfunction "1_1") (pintype "passive"))
      (node (ref "J1") (pin "14") (pinfunction "14_14") (pintype "bidirectional"))
      (node (ref "J4") (pin "P3") (pinfunction "CMD_P3") (pintype "bidirectional"))
      (node (ref "R7") (pin "1") (pinfunction "1_1") (pintype "passive"))
      (node (ref "TP7") (pin "TP") (pinfunction "TP_TP") (pintype "input"))
      (node (ref "U1") (pin "5") (pinfunction "DI(IO0)_5") (pintype "bidirectional"))
      (node (ref "U2") (pin "7") (pinfunction "IO7_7") (pintype "bidirectional"))
    )
    (net (code "21") (name "Net-(CHG_LED-PadC)") (class "Default")
      (node (ref "CHG_LED") (pin "C") (pinfunction "C_C") (pintype "passive"))
      (node (ref "R1_BAT") (pin "2") (pinfunction "2_2") (pintype "passive"))
    )
    (net (code "22") (name "Net-(D2-CATHODE)") (class "Default")
      (node (ref "C1_BAT1") (pin "1") (pinfunction "1_1") (pintype "passive"))
      (node (ref "D2") (pin "1") (pinfunction "CATHODE_1") (pintype "bidirectional"))
      (node (ref "IC4") (pin "1") (pinfunction "VIN_1") (pintype "bidirectional"))
      (node (ref "IC4") (pin "3") (pinfunction "CE_3") (pintype "bidirectional"))
      (node (ref "Q1") (pin "2") (pinfunction "S_2") (pintype "bidirectional"))
    )
    (net (code "23") (name "Net-(D3-A)") (class "Default")
      (node (ref "C4") (pin "1") (pinfunction "1_1") (pintype "passive"))
      (node (ref "D3") (pin "2") (pinfunction "A_2") (pintype "bidirectional"))
      (node (ref "D4") (pin "1") (pinfunction "K_1") (pintype "bidirectional"))
    )
    (net (code "24") (name "Net-(D7-CATHODE)") (class "Default")
      (node (ref "D7") (pin "1") (pinfunction "CATHODE_1") (pintype "bidirectional"))
      (node (ref "R_CAPACITOR") (pin "1") (pinfunction "1_1") (pintype "passive"))
    )
    (net (code "25") (name "Net-(EPD_C1-Pad1)") (class "Default")
      (node (ref "EPD_C1") (pin "1") (pinfunction "1_1") (pintype "passive"))
      (node (ref "J1") (pin "4") (pinfunction "4_4") (pintype "bidirectional"))
    )
    (net (code "26") (name "Net-(EPD_C2-Pad1)") (class "Default")
      (node (ref "EPD_C2") (pin "1") (pinfunction "1_1") (pintype "passive"))
      (node (ref "J1") (pin "5") (pinfunction "5_5") (pintype "bidirectional"))
    )
    (net (code "27") (name "Net-(EPD_C6-Pad1)") (class "Default")
      (node (ref "EPD_C6") (pin "1") (pinfunction "1_1") (pintype "passive"))
      (node (ref "J1") (pin "18") (pinfunction "18_18") (pintype "bidirectional"))
    )
    (net (code "28") (name "Net-(EPD_C7-Pad1)") (class "Default")
      (node (ref "EPD_C7") (pin "1") (pinfunction "1_1") (pintype "passive"))
      (node (ref "J1") (pin "19") (pinfunction "19_19") (pintype "bidirectional"))
    )
    (net (code "29") (name "Net-(EPD_C8-Pad1)") (class "Default")
      (node (ref "EPD_C8") (pin "1") (pinfunction "1_1") (pintype "passive"))
      (node (ref "J1") (pin "20") (pinfunction "20_20") (pintype "bidirectional"))
    )
    (net (code "30") (name "Net-(EPD_C10-Pad1)") (class "Default")
      (node (ref "EPD_C10") (pin "1") (pinfunction "1_1") (pintype "passive"))
      (node (ref "J1") (pin "22") (pinfunction "22_22") (pintype "bidirectional"))
    )
    (net (code "31") (name "Net-(EPD_C12-Pad1)") (class "Default")
      (node (ref "EPD_C12") (pin "1") (pinfunction "1_1") (pintype "passive"))
      (node (ref "J1") (pin "24") (pinfunction "24_24") (pintype "bidirectional"))
    )
    (net (code "32") (name "Net-(IC1-CT)") (class "Default")
      (node (ref "C_DELAY") (pin "1") (pinfunction "1_1") (pintype "passive"))
      (node (ref "IC1") (pin "5") (pinfunction "CT_5") (pintype "bidirectional"))
    )
    (net (code "33") (name "Net-(J2-PadA5)") (class "Default")
      (node (ref "J2") (pin "A5") (pinfunction "A5_A5") (pintype "bidirectional"))
      (node (ref "R2-USB1") (pin "2") (pinfunction "2_2") (pintype "passive"))
    )
    (net (code "34") (name "Net-(J2-PadB5)") (class "Default")
      (node (ref "J2") (pin "B5") (pinfunction "B5_B5") (pintype "bidirectional"))
      (node (ref "R2-USB") (pin "2") (pinfunction "2_2") (pintype "passive"))
    )
    (net (code "35") (name "Net-(MCP73831-PROG)") (class "Default")
      (node (ref "MCP73831") (pin "5") (pinfunction "PROG_5") (pintype "input"))
      (node (ref "R2_BAT") (pin "1") (pinfunction "1_1") (pintype "passive"))
    )
    (net (code "36") (name "Net-(MCP73831-STAT)") (class "Default")
      (node (ref "MCP73831") (pin "1") (pinfunction "STAT_1") (pintype "output"))
      (node (ref "R1_BAT") (pin "1") (pinfunction "1_1") (pintype "passive"))
    )
    (net (code "37") (name "PREVGH") (class "Default")
      (node (ref "D5") (pin "1") (pinfunction "K_1") (pintype "bidirectional"))
      (node (ref "EPD_C9") (pin "1") (pinfunction "1_1") (pintype "passive"))
      (node (ref "J1") (pin "21") (pinfunction "21_21") (pintype "bidirectional"))
    )
    (net (code "38") (name "PREVGL") (class "Default")
      (node (ref "D4") (pin "2") (pinfunction "A_2") (pintype "bidirectional"))
      (node (ref "EPD_C11") (pin "1") (pinfunction "1_1") (pintype "passive"))
      (node (ref "J1") (pin "23") (pinfunction "23_23") (pintype "bidirectional"))
    )
    (net (code "39") (name "RESE") (class "Default")
      (node (ref "J1") (pin "3") (pinfunction "3_3") (pintype "bidirectional"))
      (node (ref "Q3") (pin "2") (pinfunction "S_2") (pintype "bidirectional"))
      (node (ref "R3") (pin "1") (pinfunction "1_1") (pintype "passive"))
    )
    (net (code "40") (name "RESE'") (class "Default")
      (node (ref "R2") (pin "2") (pinfunction "2_2") (pintype "passive"))
      (node (ref "R3") (pin "2") (pinfunction "2_2") (pintype "passive"))
      (node (ref "SJ1") (pin "2") (pinfunction "2_2") (pintype "passive"))
    )
    (net (code "41") (name "RESET") (class "Default")
      (node (ref "C5") (pin "1") (pinfunction "1_1") (pintype "passive"))
      (node (ref "IC1") (pin "1") (pinfunction "VOUT_1") (pintype "bidirectional"))
      (node (ref "RESET_BUTTON") (pin "3") (pinfunction "3_3") (pintype "passive"))
      (node (ref "RESET_BUTTON") (pin "4") (pinfunction "4_4") (pintype "passive"))
      (node (ref "R_RESET") (pin "2") (pinfunction "2_2") (pintype "passive"))
      (node (ref "U2") (pin "3") (pinfunction "EN_3") (pintype "input"))
    )
    (net (code "42") (name "RTC_RST") (class "Default")
      (node (ref "U2") (pin "16") (pinfunction "IO18_16") (pintype "bidirectional"))
      (node (ref "U3") (pin "4") (pinfunction "~{RST}_4") (pintype "input"))
    )
    (net (code "43") (name "RX") (class "Default")
      (node (ref "TP2") (pin "TP") (pinfunction "TP_TP") (pintype "input"))
      (node (ref "U2") (pin "24") (pinfunction "RXD0/GPIO17_24") (pintype "bidirectional"))
    )
    (net (code "44") (name "SCK") (class "Default")
      (node (ref "D10") (pin "1") (pinfunction "1_1") (pintype "passive"))
      (node (ref "J1") (pin "13") (pinfunction "13_13") (pintype "bidirectional"))
      (node (ref "J4") (pin "P5") (pinfunction "CLK_P5") (pintype "bidirectional"))
      (node (ref "R6") (pin "1") (pinfunction "1_1") (pintype "passive"))
      (node (ref "TP8") (pin "TP") (pinfunction "TP_TP") (pintype "input"))
      (node (ref "U1") (pin "6") (pinfunction "CLK_6") (pintype "input"))
      (node (ref "U2") (pin "6") (pinfunction "IO6_6") (pintype "bidirectional"))
    )
    (net (code "45") (name "SCL") (class "Default")
      (node (ref "J3") (pin "4") (pinfunction "4_4") (pintype "passive"))
      (node (ref "R2-PINH") (pin "1") (pinfunction "1_1") (pintype "passive"))
      (node (ref "SENSOR2") (pin "4") (pinfunction "SCK_4") (pintype "input"))
      (node (ref "U2") (pin "20") (pinfunction "IO22_20") (pintype "bidirectional"))
      (node (ref "U3") (pin "16") (pinfunction "SCL_16") (pintype "input"))
      (node (ref "U4") (pin "7") (pinfunction "SCL_7") (pintype "input"))
    )
    (net (code "46") (name "SDA") (class "Default")
      (node (ref "J3") (pin "3") (pinfunction "3_3") (pintype "passive"))
      (node (ref "R1_PINH") (pin "1") (pinfunction "1_1") (pintype "passive"))
      (node (ref "SENSOR2") (pin "3") (pinfunction "SDI_3") (pintype "bidirectional"))
      (node (ref "U2") (pin "19") (pinfunction "IO21_19") (pintype "bidirectional"))
      (node (ref "U3") (pin "15") (pinfunction "SDA_15") (pintype "bidirectional"))
      (node (ref "U4") (pin "8") (pinfunction "SDA_8") (pintype "bidirectional"))
    )
    (net (code "47") (name "SRC") (class "Default")
      (node (ref "C4") (pin "2") (pinfunction "2_2") (pintype "passive"))
      (node (ref "D5") (pin "2") (pinfunction "A_2") (pintype "bidirectional"))
      (node (ref "L1") (pin "1") (pinfunction "1_1") (pintype "passive"))
      (node (ref "Q3") (pin "3") (pinfunction "D_3") (pintype "bidirectional"))
    )
    (net (code "48") (name "SS_SD") (class "Default")
      (node (ref "D8") (pin "1") (pinfunction "1_1") (pintype "passive"))
      (node (ref "J4") (pin "P2") (pinfunction "CD/DAT3_P2") (pintype "bidirectional"))
      (node (ref "R10") (pin "1") (pinfunction "1_1") (pintype "passive"))
      (node (ref "U2") (pin "4") (pinfunction "IO4_4") (pintype "bidirectional"))
    )
    (net (code "49") (name "TX") (class "Default")
      (node (ref "TP1") (pin "TP") (pinfunction "TP_TP") (pintype "input"))
      (node (ref "U2") (pin "25") (pinfunction "TXD0/GPIO16_25") (pintype "bidirectional"))
    )
    (net (code "50") (name "USB_D+") (class "Default")
      (node (ref "D1") (pin "1") (pinfunction "I/O1_1_1") (pintype "bidirectional"))
      (node (ref "U2") (pin "14") (pinfunction "IO13_14") (pintype "bidirectional"))
    )
    (net (code "51") (name "USB_D-") (class "Default")
      (node (ref "D1") (pin "3") (pinfunction "I/O2_1_3") (pintype "bidirectional"))
      (node (ref "U2") (pin "13") (pinfunction "IO12_13") (pintype "bidirectional"))
    )
    (net (code "52") (name "VBAT") (class "Default")
      (node (ref "C2_BAT") (pin "1") (pinfunction "1_1") (pintype "passive"))
      (node (ref "MCP73831") (pin "3") (pinfunction "VBAT_3") (pintype "power_in"))
      (node (ref "Q1") (pin "3") (pinfunction "D_3") (pintype "bidirectional"))
      (node (ref "TP3") (pin "TP") (pinfunction "TP_TP") (pintype "input"))
      (node (ref "U4") (pin "2") (pinfunction "CELL_2") (pintype "power_in"))
      (node (ref "U4") (pin "3") (pinfunction "VDD_3") (pintype "power_in"))
    )
    (net (code "53") (name "VBUS") (class "Default")
      (node (ref "C1_BAT") (pin "1") (pinfunction "1_1") (pintype "passive"))
      (node (ref "C4_USB") (pin "1") (pinfunction "1_1") (pintype "passive"))
      (node (ref "C5_USB") (pin "1") (pinfunction "1_1") (pintype "passive"))
      (node (ref "CHG_LED") (pin "A") (pinfunction "A_A") (pintype "passive"))
      (node (ref "D1") (pin "5") (pinfunction "VBUS_5") (pintype "bidirectional"))
      (node (ref "D2") (pin "2") (pinfunction "ANODE_2") (pintype "bidirectional"))
      (node (ref "MCP73831") (pin "4") (pinfunction "VIN_4") (pintype "power_in"))
      (node (ref "PFMF.050.1") (pin "2") (pinfunction "2_2") (pintype "passive"))
      (node (ref "Q1") (pin "1") (pinfunction "G_1") (pintype "bidirectional"))
      (node (ref "R1_PWRUSB") (pin "2") (pinfunction "2_2") (pintype "passive"))
      (node (ref "TP14") (pin "TP") (pinfunction "TP_TP") (pintype "input"))
    )
    (net (code "54") (name "VRTC") (class "Default")
      (node (ref "C10_SUPERCAP") (pin "2") (pinfunction "2_2") (pintype "passive"))
      (node (ref "C8") (pin "1") (pinfunction "1_1") (pintype "passive"))
      (node (ref "R_CAPACITOR") (pin "2") (pinfunction "2_2") (pintype "passive"))
      (node (ref "U3") (pin "14") (pinfunction "VBAT_14") (pintype "power_in"))
    )
    (net (code "55") (name "VUSB") (class "Default")
      (node (ref "J2") (pin "A4") (pinfunction "A4_A4") (pintype "bidirectional"))
      (node (ref "J2") (pin "A9") (pinfunction "A9_A9") (pintype "bidirectional"))
      (node (ref "J2") (pin "B4") (pinfunction "B4_B4") (pintype "bidirectional"))
      (node (ref "J2") (pin "B9") (pinfunction "B9_B9") (pintype "bidirectional"))
      (node (ref "PFMF.050.1") (pin "1") (pinfunction "1_1") (pintype "passive"))
    )
    (net (code "56") (name "unconnected-(IC1-NC-Pad4)") (class "Default")
      (node (ref "IC1") (pin "4") (pinfunction "NC_4") (pintype "no_connect"))
    )
    (net (code "57") (name "unconnected-(IC4-NC-Pad4)") (class "Default")
      (node (ref "IC4") (pin "4") (pinfunction "NC_4") (pintype "no_connect"))
    )
    (net (code "58") (name "unconnected-(J1-Pad1)") (class "Default")
      (node (ref "J1") (pin "1") (pinfunction "1_1") (pintype "bidirectional"))
    )
    (net (code "59") (name "unconnected-(J1-Pad6)") (class "Default")
      (node (ref "J1") (pin "6") (pinfunction "6_6") (pintype "bidirectional"))
    )
    (net (code "60") (name "unconnected-(J1-Pad7)") (class "Default")
      (node (ref "J1") (pin "7") (pinfunction "7_7") (pintype "bidirectional"))
    )
    (net (code "61") (name "unconnected-(J2-PadA8)") (class "Default")
      (node (ref "J2") (pin "A8") (pinfunction "A8_A8") (pintype "bidirectional"))
    )
    (net (code "62") (name "unconnected-(J2-PadB8)") (class "Default")
      (node (ref "J2") (pin "B8") (pinfunction "B8_B8") (pintype "bidirectional"))
    )
    (net (code "63") (name "unconnected-(J4-DAT1-PadP8)") (class "Default")
      (node (ref "J4") (pin "P8") (pinfunction "DAT1_P8") (pintype "bidirectional"))
    )
    (net (code "64") (name "unconnected-(J4-DAT2-PadP1)") (class "Default")
      (node (ref "J4") (pin "P1") (pinfunction "DAT2_P1") (pintype "bidirectional"))
    )
    (net (code "65") (name "unconnected-(J4-DETECTION_1-PadS1)") (class "Default")
      (node (ref "J4") (pin "S1") (pinfunction "DETECTION_1_S1") (pintype "bidirectional"))
    )
    (net (code "66") (name "unconnected-(J4-DETECTION_2-PadS2)") (class "Default")
      (node (ref "J4") (pin "S2") (pinfunction "DETECTION_2_S2") (pintype "bidirectional"))
    )
    (net (code "67") (name "unconnected-(U2-NC-Pad22)") (class "Default")
      (node (ref "U2") (pin "22") (pinfunction "NC_22") (pintype "no_connect"))
    )
    (net (code "68") (name "unconnected-(U4-~{ALERT}-Pad5)") (class "Default")
      (node (ref "U4") (pin "5") (pinfunction "~{ALERT}_5") (pintype "output"))
    )
  )
)
